# SUSTAINA-Control-Switches-Board.net
KiCad netlist of a schematic drawn in EAGLE
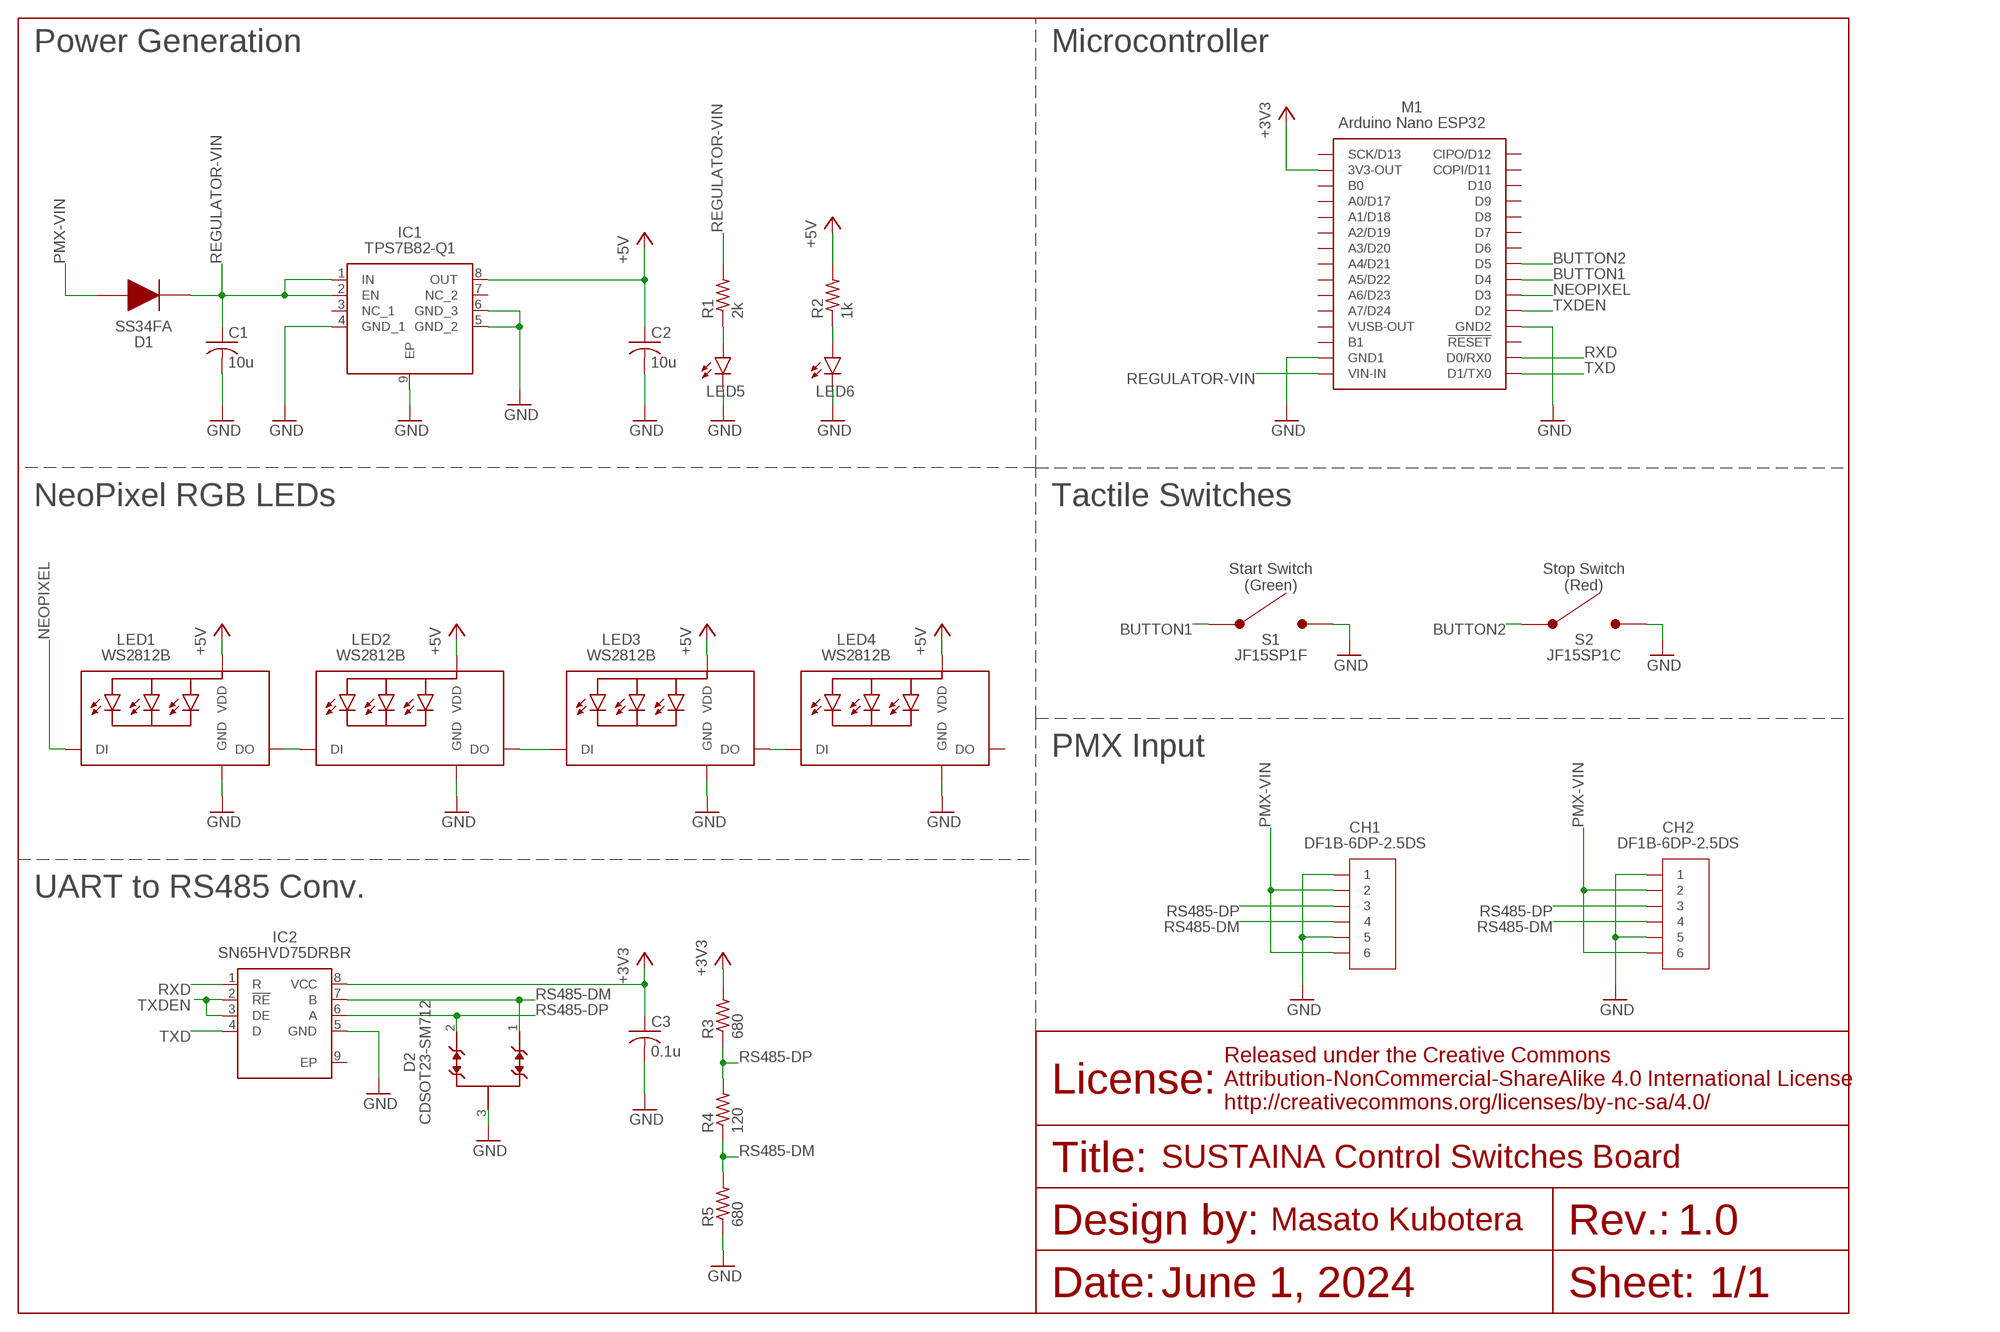
[diagram p0: schematic, sheet 1]

(export (version "E")
  (design (tool "Eeschema 10.0.6"))
  (components
    (comp (ref "C1")
      (value "10u")
      (footprint "eagle-import:C0603")
      (libsource (lib "eagle-import") (part "C-USC0603"))
    )
    (comp (ref "C2")
      (value "10u")
      (footprint "eagle-import:C0603")
      (libsource (lib "eagle-import") (part "C-USC0603"))
    )
    (comp (ref "C3")
      (value "0.1u")
      (footprint "eagle-import:C0603")
      (libsource (lib "eagle-import") (part "C-USC0603"))
    )
    (comp (ref "CH1")
      (value "DF1B-6DP-2.5DS")
      (footprint "eagle-import:DF1B-6DP-2.5DS")
      (libsource (lib "eagle-import") (part "DF1B-6DP-2.5DS"))
    )
    (comp (ref "CH2")
      (value "DF1B-6DP-2.5DS")
      (footprint "eagle-import:DF1B-6DP-2.5DS")
      (libsource (lib "eagle-import") (part "DF1B-6DP-2.5DS"))
    )
    (comp (ref "D1")
      (value "SS34FA")
      (footprint "eagle-import:SS34FA")
      (libsource (lib "eagle-import") (part "SS34FA"))
    )
    (comp (ref "D2")
      (value "CDSOT23-SM712")
      (footprint "eagle-import:SOT-23-3")
      (libsource (lib "eagle-import") (part "CDSOT23-SM712"))
    )
    (comp (ref "IC1")
      (value "TPS7B82-Q1")
      (footprint "eagle-import:SOP65P490X110-9N")
      (libsource (lib "eagle-import") (part "TPS7B82-Q1"))
    )
    (comp (ref "IC2")
      (value "SN65HVD75DRBR")
      (footprint "eagle-import:SON65P300X300X100-9N")
      (libsource (lib "eagle-import") (part "SN65HVD75DRBR"))
    )
    (comp (ref "LED1")
      (value "WS2812B")
      (footprint "eagle-import:WS2812B")
      (libsource (lib "eagle-import") (part "WS2812B"))
    )
    (comp (ref "LED2")
      (value "WS2812B")
      (footprint "eagle-import:WS2812B")
      (libsource (lib "eagle-import") (part "WS2812B"))
    )
    (comp (ref "LED3")
      (value "WS2812B")
      (footprint "eagle-import:WS2812B")
      (libsource (lib "eagle-import") (part "WS2812B"))
    )
    (comp (ref "LED4")
      (value "WS2812B")
      (footprint "eagle-import:WS2812B")
      (libsource (lib "eagle-import") (part "WS2812B"))
    )
    (comp (ref "LED5")
      (value "LEDSML0603")
      (footprint "eagle-import:SML0603")
      (libsource (lib "eagle-import") (part "LEDSML0603"))
    )
    (comp (ref "LED6")
      (value "LEDSML0603")
      (footprint "eagle-import:SML0603")
      (libsource (lib "eagle-import") (part "LEDSML0603"))
    )
    (comp (ref "M1")
      (value "NANO-ESP32")
      (footprint "eagle-import:NANO-ESP32")
      (libsource (lib "eagle-import") (part "NANO-ESP32"))
    )
    (comp (ref "R1")
      (value "2k")
      (footprint "eagle-import:R0603")
      (libsource (lib "eagle-import") (part "R-US_R0603"))
    )
    (comp (ref "R2")
      (value "1k")
      (footprint "eagle-import:R0603")
      (libsource (lib "eagle-import") (part "R-US_R0603"))
    )
    (comp (ref "R3")
      (value "680")
      (footprint "eagle-import:R0603")
      (libsource (lib "eagle-import") (part "R-US_R0603"))
    )
    (comp (ref "R4")
      (value "120")
      (footprint "eagle-import:R0603")
      (libsource (lib "eagle-import") (part "R-US_R0603"))
    )
    (comp (ref "R5")
      (value "680")
      (footprint "eagle-import:R0603")
      (libsource (lib "eagle-import") (part "R-US_R0603"))
    )
    (comp (ref "S1")
      (value "JF15SP1F")
      (footprint "eagle-import:JF15SP1")
      (libsource (lib "eagle-import") (part "JF15SP1F"))
    )
    (comp (ref "S2")
      (value "JF15SP1C")
      (footprint "eagle-import:JF15SP1")
      (libsource (lib "eagle-import") (part "JF15SP1C"))
    )
  )
  (nets
    (net (code "1") (name "+3V3") (class "Default")
      (node (ref "C3") (pin "1") (pinfunction "1_1") (pintype "passive"))
      (node (ref "IC2") (pin "8") (pinfunction "VCC_8") (pintype "bidirectional"))
      (node (ref "M1") (pin "3V3-OUT") (pinfunction "3V3-OUT_3V3-OUT") (pintype "bidirectional"))
      (node (ref "R3") (pin "2") (pinfunction "2_2") (pintype "passive"))
    )
    (net (code "2") (name "+5V") (class "Default")
      (node (ref "C2") (pin "1") (pinfunction "1_1") (pintype "passive"))
      (node (ref "IC1") (pin "8") (pinfunction "OUT_8") (pintype "bidirectional"))
      (node (ref "LED1") (pin "1-VDD") (pinfunction "VDD_1-VDD") (pintype "power_in"))
      (node (ref "LED2") (pin "1-VDD") (pinfunction "VDD_1-VDD") (pintype "power_in"))
      (node (ref "LED3") (pin "1-VDD") (pinfunction "VDD_1-VDD") (pintype "power_in"))
      (node (ref "LED4") (pin "1-VDD") (pinfunction "VDD_1-VDD") (pintype "power_in"))
      (node (ref "R2") (pin "2") (pinfunction "2_2") (pintype "passive"))
    )
    (net (code "3") (name "/BUTTON1") (class "Default")
      (node (ref "M1") (pin "D4") (pinfunction "D4_D4") (pintype "bidirectional"))
      (node (ref "S1") (pin "1") (pinfunction "P$1_1") (pintype "bidirectional"))
      (node (ref "S1") (pin "2") (pinfunction "P$1_2") (pintype "bidirectional"))
    )
    (net (code "4") (name "/BUTTON2") (class "Default")
      (node (ref "M1") (pin "D5") (pinfunction "D5_D5") (pintype "bidirectional"))
      (node (ref "S2") (pin "1") (pinfunction "P$1_1") (pintype "bidirectional"))
      (node (ref "S2") (pin "2") (pinfunction "P$1_2") (pintype "bidirectional"))
    )
    (net (code "5") (name "/NEOPIXEL") (class "Default")
      (node (ref "LED1") (pin "4-DIN") (pinfunction "DI_4-DIN") (pintype "input"))
      (node (ref "M1") (pin "D3") (pinfunction "D3_D3") (pintype "bidirectional"))
    )
    (net (code "6") (name "/PMX-VIN") (class "Default")
      (node (ref "CH1") (pin "2") (pinfunction "2_2") (pintype "bidirectional"))
      (node (ref "CH1") (pin "6") (pinfunction "6_6") (pintype "bidirectional"))
      (node (ref "CH2") (pin "2") (pinfunction "2_2") (pintype "bidirectional"))
      (node (ref "CH2") (pin "6") (pinfunction "6_6") (pintype "bidirectional"))
      (node (ref "D1") (pin "2") (pinfunction "2_2") (pintype "bidirectional"))
    )
    (net (code "7") (name "/REGULATOR-VIN") (class "Default")
      (node (ref "C1") (pin "1") (pinfunction "1_1") (pintype "passive"))
      (node (ref "D1") (pin "1") (pinfunction "1_1") (pintype "bidirectional"))
      (node (ref "IC1") (pin "1") (pinfunction "IN_1") (pintype "bidirectional"))
      (node (ref "IC1") (pin "2") (pinfunction "EN_2") (pintype "bidirectional"))
      (node (ref "M1") (pin "VIN-IN") (pinfunction "VIN-IN_VIN-IN") (pintype "bidirectional"))
      (node (ref "R1") (pin "2") (pinfunction "2_2") (pintype "passive"))
    )
    (net (code "8") (name "/RS485-DM") (class "Default")
      (node (ref "CH1") (pin "4") (pinfunction "4_4") (pintype "bidirectional"))
      (node (ref "CH2") (pin "4") (pinfunction "4_4") (pintype "bidirectional"))
      (node (ref "D2") (pin "1") (pinfunction "1_1") (pintype "bidirectional"))
      (node (ref "IC2") (pin "7") (pinfunction "B_7") (pintype "bidirectional"))
      (node (ref "R4") (pin "1") (pinfunction "1_1") (pintype "passive"))
      (node (ref "R5") (pin "2") (pinfunction "2_2") (pintype "passive"))
    )
    (net (code "9") (name "/RS485-DP") (class "Default")
      (node (ref "CH1") (pin "3") (pinfunction "3_3") (pintype "bidirectional"))
      (node (ref "CH2") (pin "3") (pinfunction "3_3") (pintype "bidirectional"))
      (node (ref "D2") (pin "2") (pinfunction "2_2") (pintype "bidirectional"))
      (node (ref "IC2") (pin "6") (pinfunction "A_6") (pintype "bidirectional"))
      (node (ref "R3") (pin "1") (pinfunction "1_1") (pintype "passive"))
      (node (ref "R4") (pin "2") (pinfunction "2_2") (pintype "passive"))
    )
    (net (code "10") (name "/RXD") (class "Default")
      (node (ref "IC2") (pin "1") (pinfunction "R_1") (pintype "bidirectional"))
      (node (ref "M1") (pin "D0/RX0") (pinfunction "D0/RX0_D0/RX0") (pintype "bidirectional"))
    )
    (net (code "11") (name "/TXD") (class "Default")
      (node (ref "IC2") (pin "4") (pinfunction "D_4") (pintype "bidirectional"))
      (node (ref "M1") (pin "D1/TX0") (pinfunction "D1/TX0_D1/TX0") (pintype "bidirectional"))
    )
    (net (code "12") (name "/TXDEN") (class "Default")
      (node (ref "IC2") (pin "2") (pinfunction "~{RE}_2") (pintype "bidirectional"))
      (node (ref "IC2") (pin "3") (pinfunction "DE_3") (pintype "bidirectional"))
      (node (ref "M1") (pin "D2") (pinfunction "D2_D2") (pintype "bidirectional"))
    )
    (net (code "13") (name "GND") (class "Default")
      (node (ref "C1") (pin "2") (pinfunction "2_2") (pintype "passive"))
      (node (ref "C2") (pin "2") (pinfunction "2_2") (pintype "passive"))
      (node (ref "C3") (pin "2") (pinfunction "2_2") (pintype "passive"))
      (node (ref "CH1") (pin "1") (pinfunction "1_1") (pintype "bidirectional"))
      (node (ref "CH1") (pin "5") (pinfunction "5_5") (pintype "bidirectional"))
      (node (ref "CH2") (pin "1") (pinfunction "1_1") (pintype "bidirectional"))
      (node (ref "CH2") (pin "5") (pinfunction "5_5") (pintype "bidirectional"))
      (node (ref "D2") (pin "3") (pinfunction "3_3") (pintype "bidirectional"))
      (node (ref "IC1") (pin "4") (pinfunction "GND_1_4") (pintype "bidirectional"))
      (node (ref "IC1") (pin "5") (pinfunction "GND_2_5") (pintype "bidirectional"))
      (node (ref "IC1") (pin "6") (pinfunction "GND_3_6") (pintype "bidirectional"))
      (node (ref "IC1") (pin "9") (pinfunction "EP_9") (pintype "bidirectional"))
      (node (ref "IC2") (pin "5") (pinfunction "GND_5") (pintype "bidirectional"))
      (node (ref "LED1") (pin "3-GND") (pinfunction "GND_3-GND") (pintype "power_in"))
      (node (ref "LED2") (pin "3-GND") (pinfunction "GND_3-GND") (pintype "power_in"))
      (node (ref "LED3") (pin "3-GND") (pinfunction "GND_3-GND") (pintype "power_in"))
      (node (ref "LED4") (pin "3-GND") (pinfunction "GND_3-GND") (pintype "power_in"))
      (node (ref "LED5") (pin "C") (pinfunction "C_C") (pintype "passive"))
      (node (ref "LED6") (pin "C") (pinfunction "C_C") (pintype "passive"))
      (node (ref "M1") (pin "GND1") (pinfunction "GND1_GND1") (pintype "bidirectional"))
      (node (ref "M1") (pin "GND2") (pinfunction "GND2_GND2") (pintype "bidirectional"))
      (node (ref "R5") (pin "1") (pinfunction "1_1") (pintype "passive"))
      (node (ref "S1") (pin "3") (pinfunction "P$2_3") (pintype "bidirectional"))
      (node (ref "S1") (pin "4") (pinfunction "P$2_4") (pintype "bidirectional"))
      (node (ref "S2") (pin "3") (pinfunction "P$2_3") (pintype "bidirectional"))
      (node (ref "S2") (pin "4") (pinfunction "P$2_4") (pintype "bidirectional"))
    )
    (net (code "14") (name "Net-(LED1-DO)") (class "Default")
      (node (ref "LED1") (pin "2-DOUT") (pinfunction "DO_2-DOUT") (pintype "output"))
      (node (ref "LED2") (pin "4-DIN") (pinfunction "DI_4-DIN") (pintype "input"))
    )
    (net (code "15") (name "Net-(LED2-DO)") (class "Default")
      (node (ref "LED2") (pin "2-DOUT") (pinfunction "DO_2-DOUT") (pintype "output"))
      (node (ref "LED3") (pin "4-DIN") (pinfunction "DI_4-DIN") (pintype "input"))
    )
    (net (code "16") (name "Net-(LED3-DO)") (class "Default")
      (node (ref "LED3") (pin "2-DOUT") (pinfunction "DO_2-DOUT") (pintype "output"))
      (node (ref "LED4") (pin "4-DIN") (pinfunction "DI_4-DIN") (pintype "input"))
    )
    (net (code "17") (name "Net-(LED5-PadA)") (class "Default")
      (node (ref "LED5") (pin "A") (pinfunction "A_A") (pintype "passive"))
      (node (ref "R1") (pin "1") (pinfunction "1_1") (pintype "passive"))
    )
    (net (code "18") (name "Net-(LED6-PadA)") (class "Default")
      (node (ref "LED6") (pin "A") (pinfunction "A_A") (pintype "passive"))
      (node (ref "R2") (pin "1") (pinfunction "1_1") (pintype "passive"))
    )
    (net (code "19") (name "unconnected-(IC1-NC_1-Pad3)") (class "Default")
      (node (ref "IC1") (pin "3") (pinfunction "NC_1_3") (pintype "no_connect"))
    )
    (net (code "20") (name "unconnected-(IC1-NC_2-Pad7)") (class "Default")
      (node (ref "IC1") (pin "7") (pinfunction "NC_2_7") (pintype "no_connect"))
    )
    (net (code "21") (name "unconnected-(IC2-EP-Pad9)") (class "Default")
      (node (ref "IC2") (pin "9") (pinfunction "EP_9") (pintype "bidirectional"))
    )
    (net (code "22") (name "unconnected-(LED4-DO-Pad2-DOUT)") (class "Default")
      (node (ref "LED4") (pin "2-DOUT") (pinfunction "DO_2-DOUT") (pintype "output"))
    )
    (net (code "23") (name "unconnected-(M1-PadA0{slash}D17)") (class "Default")
      (node (ref "M1") (pin "A0/D17") (pinfunction "A0/D17_A0/D17") (pintype "bidirectional"))
    )
    (net (code "24") (name "unconnected-(M1-PadA1{slash}D18)") (class "Default")
      (node (ref "M1") (pin "A1/D18") (pinfunction "A1/D18_A1/D18") (pintype "bidirectional"))
    )
    (net (code "25") (name "unconnected-(M1-PadA2{slash}D19)") (class "Default")
      (node (ref "M1") (pin "A2/D19") (pinfunction "A2/D19_A2/D19") (pintype "bidirectional"))
    )
    (net (code "26") (name "unconnected-(M1-PadA3{slash}D20)") (class "Default")
      (node (ref "M1") (pin "A3/D20") (pinfunction "A3/D20_A3/D20") (pintype "bidirectional"))
    )
    (net (code "27") (name "unconnected-(M1-PadA4{slash}D21)") (class "Default")
      (node (ref "M1") (pin "A4/D21") (pinfunction "A4/D21_A4/D21") (pintype "bidirectional"))
    )
    (net (code "28") (name "unconnected-(M1-PadA5{slash}D22)") (class "Default")
      (node (ref "M1") (pin "A5/D22") (pinfunction "A5/D22_A5/D22") (pintype "bidirectional"))
    )
    (net (code "29") (name "unconnected-(M1-PadA6{slash}D23)") (class "Default")
      (node (ref "M1") (pin "A6/D23") (pinfunction "A6/D23_A6/D23") (pintype "bidirectional"))
    )
    (net (code "30") (name "unconnected-(M1-PadA7{slash}D24)") (class "Default")
      (node (ref "M1") (pin "A7/D24") (pinfunction "A7/D24_A7/D24") (pintype "bidirectional"))
    )
    (net (code "31") (name "unconnected-(M1-PadB0)") (class "Default")
      (node (ref "M1") (pin "B0") (pinfunction "B0_B0") (pintype "bidirectional"))
    )
    (net (code "32") (name "unconnected-(M1-PadB1)") (class "Default")
      (node (ref "M1") (pin "B1") (pinfunction "B1_B1") (pintype "bidirectional"))
    )
    (net (code "33") (name "unconnected-(M1-PadCIPO{slash}D12)") (class "Default")
      (node (ref "M1") (pin "CIPO/D12") (pinfunction "CIPO/D12_CIPO/D12") (pintype "bidirectional"))
    )
    (net (code "34") (name "unconnected-(M1-PadCOPI{slash}D11)") (class "Default")
      (node (ref "M1") (pin "COPI/D11") (pinfunction "COPI/D11_COPI/D11") (pintype "bidirectional"))
    )
    (net (code "35") (name "unconnected-(M1-PadD6)") (class "Default")
      (node (ref "M1") (pin "D6") (pinfunction "D6_D6") (pintype "bidirectional"))
    )
    (net (code "36") (name "unconnected-(M1-PadD7)") (class "Default")
      (node (ref "M1") (pin "D7") (pinfunction "D7_D7") (pintype "bidirectional"))
    )
    (net (code "37") (name "unconnected-(M1-PadD8)") (class "Default")
      (node (ref "M1") (pin "D8") (pinfunction "D8_D8") (pintype "bidirectional"))
    )
    (net (code "38") (name "unconnected-(M1-PadD9)") (class "Default")
      (node (ref "M1") (pin "D9") (pinfunction "D9_D9") (pintype "bidirectional"))
    )
    (net (code "39") (name "unconnected-(M1-PadD10)") (class "Default")
      (node (ref "M1") (pin "D10") (pinfunction "D10_D10") (pintype "bidirectional"))
    )
    (net (code "40") (name "unconnected-(M1-PadSCK{slash}D13)") (class "Default")
      (node (ref "M1") (pin "SCK/D13") (pinfunction "SCK/D13_SCK/D13") (pintype "bidirectional"))
    )
    (net (code "41") (name "unconnected-(M1-PadVUSB-OUT)") (class "Default")
      (node (ref "M1") (pin "VUSB-OUT") (pinfunction "VUSB-OUT_VUSB-OUT") (pintype "bidirectional"))
    )
    (net (code "42") (name "unconnected-(M1-~{RESET}-Pad!RESET)") (class "Default")
      (node (ref "M1") (pin "!RESET") (pinfunction "~{RESET}_!RESET") (pintype "bidirectional"))
    )
  )
)
